# Power_and_Clocks.net
KiCad netlist of a schematic drawn in Altium Designer
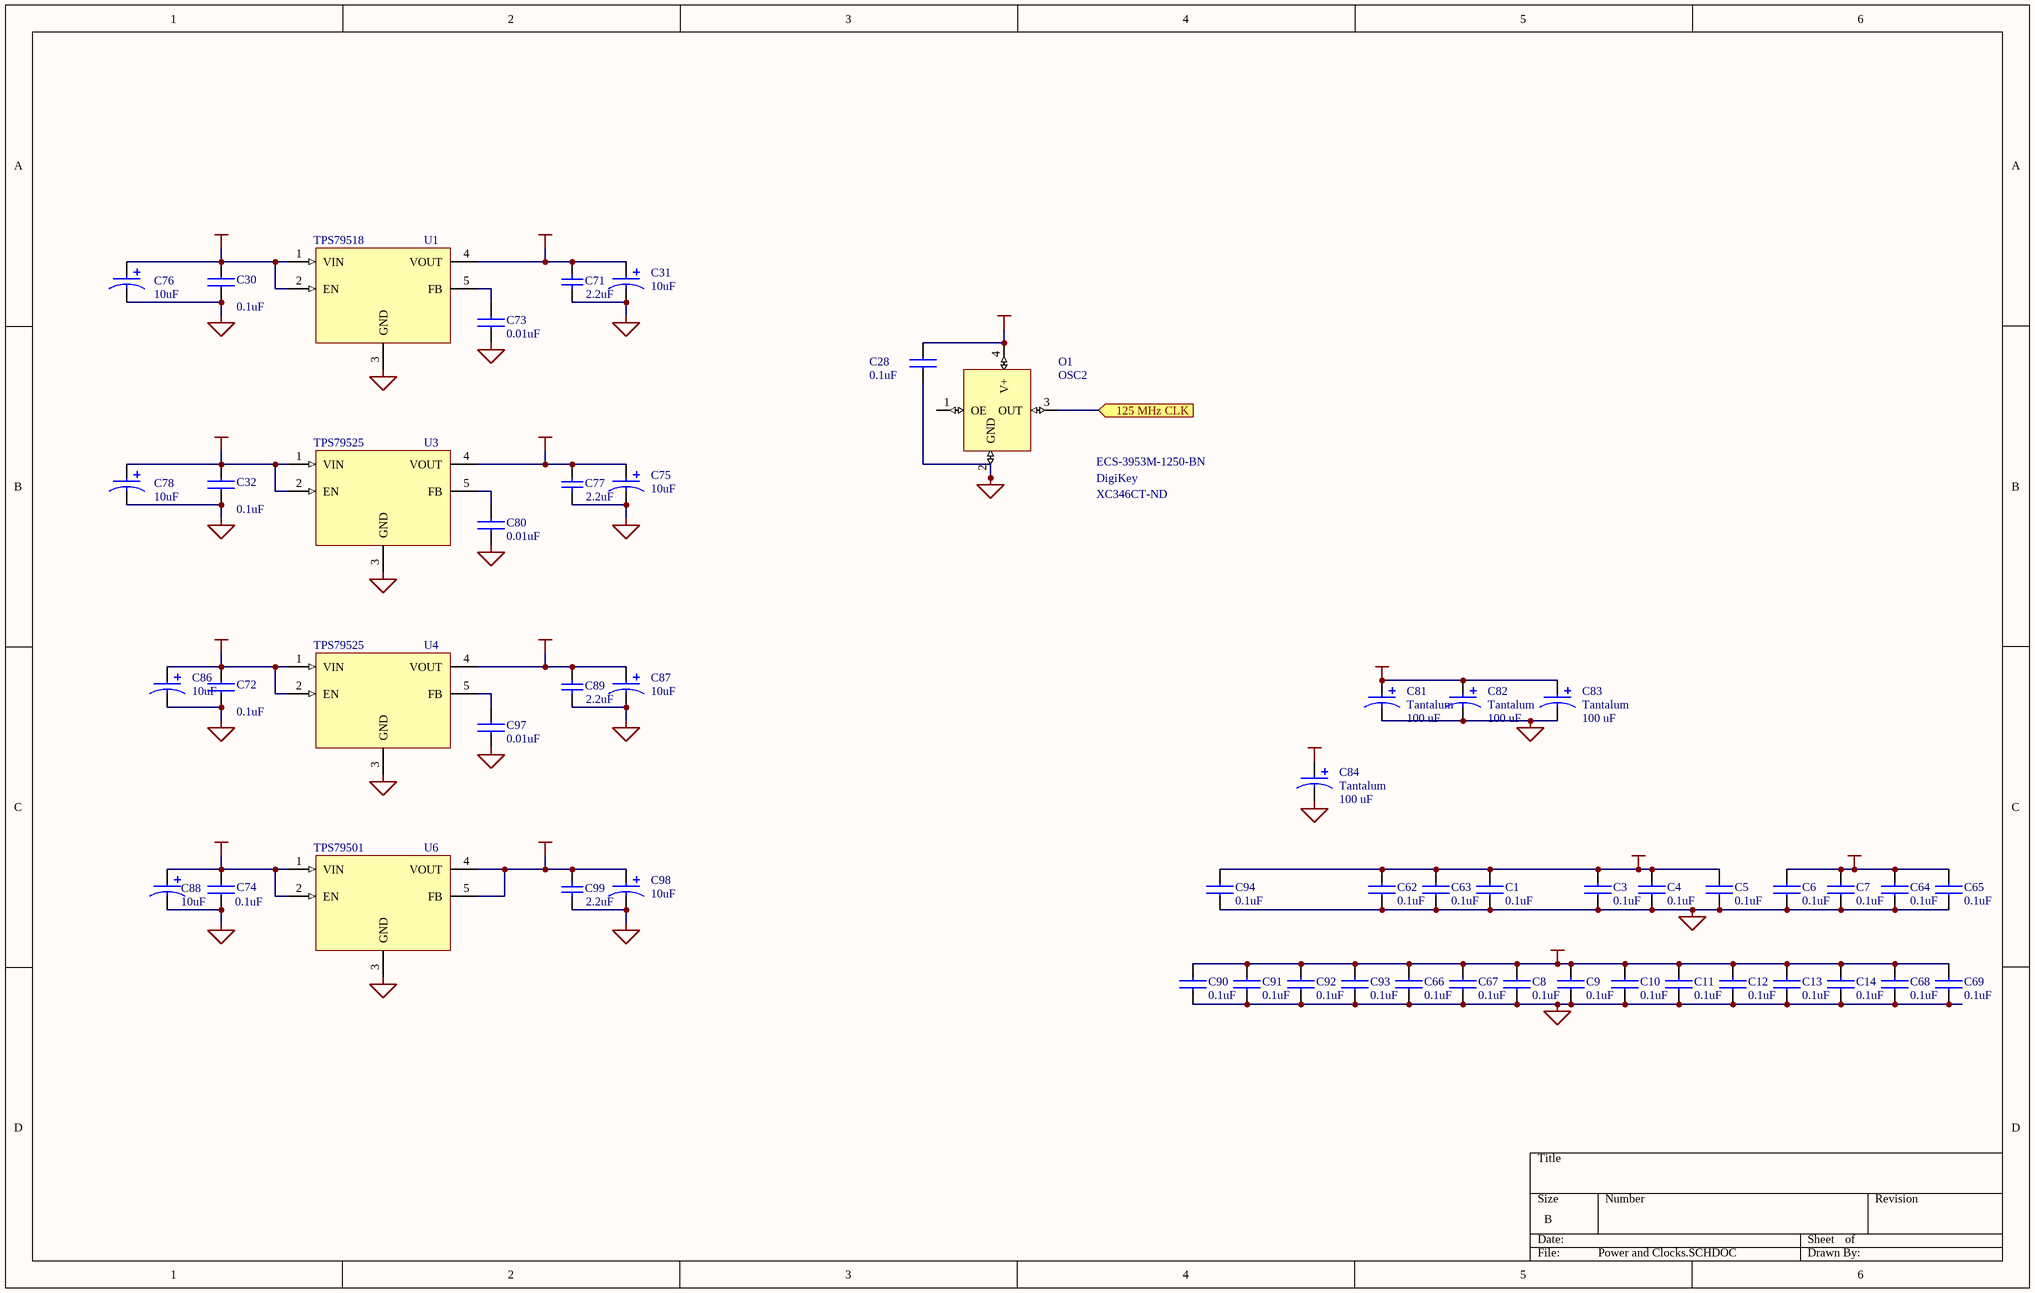
[diagram p0: Power and Clocks.SCHDOC]

(export (version "E")
  (design (tool "Eeschema 10.0.6"))
  (components
    (comp (ref "C1")
      (value "0.1uF")
      (footprint "0603")
      (description "Standard Capacitor")
      (fields (field (name "Comment") "CAPACITOR"))
      (libsource (lib "parts") (part "CAPACITOR"))
    )
    (comp (ref "C3")
      (value "0.1uF")
      (footprint "0603")
      (description "Standard Capacitor")
      (fields (field (name "Comment") "CAPACITOR"))
      (libsource (lib "parts") (part "CAPACITOR"))
    )
    (comp (ref "C4")
      (value "0.1uF")
      (footprint "0603")
      (description "Standard Capacitor")
      (fields (field (name "Comment") "CAPACITOR"))
      (libsource (lib "parts") (part "CAPACITOR"))
    )
    (comp (ref "C5")
      (value "0.1uF")
      (footprint "0603")
      (description "Standard Capacitor")
      (fields (field (name "Comment") "CAPACITOR"))
      (libsource (lib "parts") (part "CAPACITOR"))
    )
    (comp (ref "C6")
      (value "0.1uF")
      (footprint "0603")
      (description "Standard Capacitor")
      (fields (field (name "Comment") "CAPACITOR"))
      (libsource (lib "parts") (part "CAPACITOR"))
    )
    (comp (ref "C7")
      (value "0.1uF")
      (footprint "0603")
      (description "Standard Capacitor")
      (fields (field (name "Comment") "CAPACITOR"))
      (libsource (lib "parts") (part "CAPACITOR"))
    )
    (comp (ref "C8")
      (value "0.1uF")
      (footprint "0603")
      (description "Standard Capacitor")
      (fields (field (name "Comment") "CAPACITOR"))
      (libsource (lib "parts") (part "CAPACITOR"))
    )
    (comp (ref "C9")
      (value "0.1uF")
      (footprint "0603")
      (description "Standard Capacitor")
      (fields (field (name "Comment") "CAPACITOR"))
      (libsource (lib "parts") (part "CAPACITOR"))
    )
    (comp (ref "C10")
      (value "0.1uF")
      (footprint "0603")
      (description "Standard Capacitor")
      (fields (field (name "Comment") "CAPACITOR"))
      (libsource (lib "parts") (part "CAPACITOR"))
    )
    (comp (ref "C11")
      (value "0.1uF")
      (footprint "0603")
      (description "Standard Capacitor")
      (fields (field (name "Comment") "CAPACITOR"))
      (libsource (lib "parts") (part "CAPACITOR"))
    )
    (comp (ref "C12")
      (value "0.1uF")
      (footprint "0603")
      (description "Standard Capacitor")
      (fields (field (name "Comment") "CAPACITOR"))
      (libsource (lib "parts") (part "CAPACITOR"))
    )
    (comp (ref "C13")
      (value "0.1uF")
      (footprint "0603")
      (description "Standard Capacitor")
      (fields (field (name "Comment") "CAPACITOR"))
      (libsource (lib "parts") (part "CAPACITOR"))
    )
    (comp (ref "C14")
      (value "0.1uF")
      (footprint "0603")
      (description "Standard Capacitor")
      (fields (field (name "Comment") "CAPACITOR"))
      (libsource (lib "parts") (part "CAPACITOR"))
    )
    (comp (ref "C28")
      (value "0.1uF")
      (footprint "0603")
      (description "Standard Capacitor")
      (fields (field (name "Comment") "CAPACITOR"))
      (libsource (lib "parts") (part "CAPACITOR"))
    )
    (comp (ref "C30")
      (value "0.1uF")
      (footprint "0603")
      (description "Standard Capacitor")
      (fields (field (name "Comment") "CAPACITOR"))
      (libsource (lib "parts") (part "CAPACITOR"))
    )
    (comp (ref "C31")
      (value "10uF")
      (footprint "6032")
      (description "Standard Capacitor")
      (fields (field (name "Comment") "POLCAP2"))
      (libsource (lib "parts") (part "POLCAP2"))
    )
    (comp (ref "C32")
      (value "0.1uF")
      (footprint "0603")
      (description "Standard Capacitor")
      (fields (field (name "Comment") "CAPACITOR"))
      (libsource (lib "parts") (part "CAPACITOR"))
    )
    (comp (ref "C62")
      (value "0.1uF")
      (footprint "0603")
      (description "Standard Capacitor")
      (fields (field (name "Comment") "CAPACITOR"))
      (libsource (lib "parts") (part "CAPACITOR"))
    )
    (comp (ref "C63")
      (value "0.1uF")
      (footprint "0603")
      (description "Standard Capacitor")
      (fields (field (name "Comment") "CAPACITOR"))
      (libsource (lib "parts") (part "CAPACITOR"))
    )
    (comp (ref "C64")
      (value "0.1uF")
      (footprint "0603")
      (description "Standard Capacitor")
      (fields (field (name "Comment") "CAPACITOR"))
      (libsource (lib "parts") (part "CAPACITOR"))
    )
    (comp (ref "C65")
      (value "0.1uF")
      (footprint "0603")
      (description "Standard Capacitor")
      (fields (field (name "Comment") "CAPACITOR"))
      (libsource (lib "parts") (part "CAPACITOR"))
    )
    (comp (ref "C66")
      (value "0.1uF")
      (footprint "0603")
      (description "Standard Capacitor")
      (fields (field (name "Comment") "CAPACITOR"))
      (libsource (lib "parts") (part "CAPACITOR"))
    )
    (comp (ref "C67")
      (value "0.1uF")
      (footprint "0603")
      (description "Standard Capacitor")
      (fields (field (name "Comment") "CAPACITOR"))
      (libsource (lib "parts") (part "CAPACITOR"))
    )
    (comp (ref "C68")
      (value "0.1uF")
      (footprint "0603")
      (description "Standard Capacitor")
      (fields (field (name "Comment") "CAPACITOR"))
      (libsource (lib "parts") (part "CAPACITOR"))
    )
    (comp (ref "C69")
      (value "0.1uF")
      (footprint "0603")
      (description "Standard Capacitor")
      (fields (field (name "Comment") "CAPACITOR"))
      (libsource (lib "parts") (part "CAPACITOR"))
    )
    (comp (ref "C71")
      (value "2.2uF")
      (footprint "1206")
      (description "Capacitor")
      (fields
        (field (name "MANUFACTURER") "Generic Components")
        (field (name "Comment") "Cap")
        (field (name "PUBLISHER") "Altium Limited")
      )
      (libsource (lib "Miscellaneous Devices") (part "Cap"))
    )
    (comp (ref "C72")
      (value "0.1uF")
      (footprint "0603")
      (description "Standard Capacitor")
      (fields (field (name "Comment") "CAPACITOR"))
      (libsource (lib "parts") (part "CAPACITOR"))
    )
    (comp (ref "C73")
      (value "0.01uF")
      (footprint "0402")
      (description "Standard Capacitor")
      (fields (field (name "Comment") "CAPACITOR"))
      (libsource (lib "parts") (part "CAPACITOR"))
    )
    (comp (ref "C74")
      (value "0.1uF")
      (footprint "0603")
      (description "Standard Capacitor")
      (fields (field (name "Comment") "CAPACITOR"))
      (libsource (lib "parts") (part "CAPACITOR"))
    )
    (comp (ref "C75")
      (value "10uF")
      (footprint "6032")
      (description "Standard Capacitor")
      (fields (field (name "Comment") "POLCAP2"))
      (libsource (lib "parts") (part "POLCAP2"))
    )
    (comp (ref "C76")
      (value "10uF")
      (footprint "6032")
      (description "Standard Capacitor")
      (fields (field (name "Comment") "POLCAP2"))
      (libsource (lib "parts") (part "POLCAP2"))
    )
    (comp (ref "C77")
      (value "2.2uF")
      (footprint "1206")
      (description "Capacitor")
      (fields
        (field (name "MANUFACTURER") "Generic Components")
        (field (name "Comment") "Cap")
        (field (name "PUBLISHER") "Altium Limited")
      )
      (libsource (lib "Miscellaneous Devices") (part "Cap"))
    )
    (comp (ref "C78")
      (value "10uF")
      (footprint "6032")
      (description "Standard Capacitor")
      (fields (field (name "Comment") "POLCAP2"))
      (libsource (lib "parts") (part "POLCAP2"))
    )
    (comp (ref "C80")
      (value "0.01uF")
      (footprint "0402")
      (description "Standard Capacitor")
      (fields (field (name "Comment") "CAPACITOR"))
      (libsource (lib "parts") (part "CAPACITOR"))
    )
    (comp (ref "C81")
      (value "Tantalum")
      (footprint "6032")
      (description "Standard Capacitor")
      (fields (field (name "ALTIUM_VALUE") "100 uF"))
      (libsource (lib "parts") (part "POLCAP2"))
    )
    (comp (ref "C82")
      (value "Tantalum")
      (footprint "6032")
      (description "Standard Capacitor")
      (fields (field (name "ALTIUM_VALUE") "100 uF"))
      (libsource (lib "parts") (part "POLCAP2"))
    )
    (comp (ref "C83")
      (value "Tantalum")
      (footprint "6032")
      (description "Standard Capacitor")
      (fields (field (name "ALTIUM_VALUE") "100 uF"))
      (libsource (lib "parts") (part "POLCAP2"))
    )
    (comp (ref "C84")
      (value "Tantalum")
      (footprint "6032")
      (description "Standard Capacitor")
      (fields (field (name "ALTIUM_VALUE") "100 uF"))
      (libsource (lib "parts") (part "POLCAP2"))
    )
    (comp (ref "C86")
      (value "10uF")
      (footprint "6032")
      (description "Standard Capacitor")
      (fields (field (name "Comment") "POLCAP2"))
      (libsource (lib "parts") (part "POLCAP2"))
    )
    (comp (ref "C87")
      (value "10uF")
      (footprint "6032")
      (description "Standard Capacitor")
      (fields (field (name "Comment") "POLCAP2"))
      (libsource (lib "parts") (part "POLCAP2"))
    )
    (comp (ref "C88")
      (value "10uF")
      (footprint "6032")
      (description "Standard Capacitor")
      (fields (field (name "Comment") "POLCAP2"))
      (libsource (lib "parts") (part "POLCAP2"))
    )
    (comp (ref "C89")
      (value "2.2uF")
      (footprint "1206")
      (description "Capacitor")
      (fields
        (field (name "MANUFACTURER") "Generic Components")
        (field (name "Comment") "Cap")
        (field (name "PUBLISHER") "Altium Limited")
      )
      (libsource (lib "Miscellaneous Devices") (part "Cap"))
    )
    (comp (ref "C90")
      (value "0.1uF")
      (footprint "0603")
      (description "Standard Capacitor")
      (fields (field (name "Comment") "CAPACITOR"))
      (libsource (lib "parts") (part "CAPACITOR"))
    )
    (comp (ref "C91")
      (value "0.1uF")
      (footprint "0603")
      (description "Standard Capacitor")
      (fields (field (name "Comment") "CAPACITOR"))
      (libsource (lib "parts") (part "CAPACITOR"))
    )
    (comp (ref "C92")
      (value "0.1uF")
      (footprint "0603")
      (description "Standard Capacitor")
      (fields (field (name "Comment") "CAPACITOR"))
      (libsource (lib "parts") (part "CAPACITOR"))
    )
    (comp (ref "C93")
      (value "0.1uF")
      (footprint "0603")
      (description "Standard Capacitor")
      (fields (field (name "Comment") "CAPACITOR"))
      (libsource (lib "parts") (part "CAPACITOR"))
    )
    (comp (ref "C94")
      (value "0.1uF")
      (footprint "0603")
      (description "Standard Capacitor")
      (fields (field (name "Comment") "CAPACITOR"))
      (libsource (lib "parts") (part "CAPACITOR"))
    )
    (comp (ref "C97")
      (value "0.01uF")
      (footprint "0402")
      (description "Standard Capacitor")
      (fields (field (name "Comment") "CAPACITOR"))
      (libsource (lib "parts") (part "CAPACITOR"))
    )
    (comp (ref "C98")
      (value "10uF")
      (footprint "6032")
      (description "Standard Capacitor")
      (fields (field (name "Comment") "POLCAP2"))
      (libsource (lib "parts") (part "POLCAP2"))
    )
    (comp (ref "C99")
      (value "2.2uF")
      (footprint "1206")
      (description "Capacitor")
      (fields
        (field (name "MANUFACTURER") "Generic Components")
        (field (name "Comment") "Cap")
        (field (name "PUBLISHER") "Altium Limited")
      )
      (libsource (lib "Miscellaneous Devices") (part "Cap"))
    )
    (comp (ref "O1")
      (value "OSC2")
      (footprint "ECS-3953M")
      (description "ECS SMD Oscillator, ECS-3953M")
      (fields
        (field (name "PART") "ECS-3953M-1250-BN")
        (field (name "VENDOR") "DigiKey")
        (field (name "VENDORPART") "XC346CT-ND")
      )
      (libsource (lib "My devices") (part "OSC2"))
    )
    (comp (ref "U1")
      (value "TPS79518")
      (footprint "SOT223-5/Simple")
      (description "TI Ultra-low-noise LDO")
      (libsource (lib "parts") (part "TPS795XX"))
    )
    (comp (ref "U3")
      (value "TPS79525")
      (footprint "SOT223-5/Simple")
      (description "TI Ultra-low-noise LDO")
      (libsource (lib "parts") (part "TPS795XX"))
    )
    (comp (ref "U4")
      (value "TPS79525")
      (footprint "SOT223-5/Simple")
      (description "TI Ultra-low-noise LDO")
      (libsource (lib "parts") (part "TPS795XX"))
    )
    (comp (ref "U6")
      (value "TPS79501")
      (footprint "SOT223-5/Simple")
      (description "TI Ultra-low-noise LDO")
      (libsource (lib "parts") (part "TPS795XX"))
    )
  )
  (nets
    (net (code "1") (name "+1.2VCC") (class "Default")
      (node (ref "C6") (pin "2") (pintype "passive"))
      (node (ref "C64") (pin "2") (pintype "passive"))
      (node (ref "C65") (pin "2") (pintype "passive"))
      (node (ref "C7") (pin "2") (pintype "passive"))
      (node (ref "C98") (pin "1") (pintype "passive"))
      (node (ref "C99") (pin "2") (pinfunction "2_2") (pintype "passive"))
      (node (ref "U6") (pin "4") (pinfunction "VOUT_4") (pintype "power_in"))
      (node (ref "U6") (pin "5") (pinfunction "FB_5") (pintype "passive"))
    )
    (net (code "2") (name "+1.8VCC") (class "Default")
      (node (ref "C31") (pin "1") (pintype "passive"))
      (node (ref "C71") (pin "2") (pinfunction "2_2") (pintype "passive"))
      (node (ref "C84") (pin "1") (pintype "passive"))
      (node (ref "U1") (pin "4") (pinfunction "VOUT_4") (pintype "power_in"))
    )
    (net (code "3") (name "+2.5VCC") (class "Default")
      (node (ref "C1") (pin "2") (pintype "passive"))
      (node (ref "C3") (pin "2") (pintype "passive"))
      (node (ref "C4") (pin "2") (pintype "passive"))
      (node (ref "C5") (pin "2") (pintype "passive"))
      (node (ref "C62") (pin "2") (pintype "passive"))
      (node (ref "C63") (pin "2") (pintype "passive"))
      (node (ref "C75") (pin "1") (pintype "passive"))
      (node (ref "C77") (pin "2") (pinfunction "2_2") (pintype "passive"))
      (node (ref "C94") (pin "2") (pintype "passive"))
      (node (ref "U3") (pin "4") (pinfunction "VOUT_4") (pintype "power_in"))
    )
    (net (code "4") (name "+2.5VPHY") (class "Default")
      (node (ref "C87") (pin "1") (pintype "passive"))
      (node (ref "C89") (pin "2") (pinfunction "2_2") (pintype "passive"))
      (node (ref "U4") (pin "4") (pinfunction "VOUT_4") (pintype "power_in"))
    )
    (net (code "5") (name "/125 MHz CLK") (class "Default")
      (node (ref "O1") (pin "3") (pinfunction "OUT_3") (pintype "bidirectional"))
    )
    (net (code "6") (name "GND") (class "Default")
      (node (ref "C1") (pin "1") (pintype "passive"))
      (node (ref "C10") (pin "1") (pintype "passive"))
      (node (ref "C11") (pin "1") (pintype "passive"))
      (node (ref "C12") (pin "1") (pintype "passive"))
      (node (ref "C13") (pin "1") (pintype "passive"))
      (node (ref "C14") (pin "1") (pintype "passive"))
      (node (ref "C28") (pin "1") (pintype "passive"))
      (node (ref "C3") (pin "1") (pintype "passive"))
      (node (ref "C30") (pin "1") (pintype "passive"))
      (node (ref "C31") (pin "2") (pintype "passive"))
      (node (ref "C32") (pin "1") (pintype "passive"))
      (node (ref "C4") (pin "1") (pintype "passive"))
      (node (ref "C5") (pin "1") (pintype "passive"))
      (node (ref "C6") (pin "1") (pintype "passive"))
      (node (ref "C62") (pin "1") (pintype "passive"))
      (node (ref "C63") (pin "1") (pintype "passive"))
      (node (ref "C64") (pin "1") (pintype "passive"))
      (node (ref "C65") (pin "1") (pintype "passive"))
      (node (ref "C66") (pin "1") (pintype "passive"))
      (node (ref "C67") (pin "1") (pintype "passive"))
      (node (ref "C68") (pin "1") (pintype "passive"))
      (node (ref "C69") (pin "1") (pintype "passive"))
      (node (ref "C7") (pin "1") (pintype "passive"))
      (node (ref "C71") (pin "1") (pinfunction "1_1") (pintype "passive"))
      (node (ref "C72") (pin "1") (pintype "passive"))
      (node (ref "C73") (pin "1") (pintype "passive"))
      (node (ref "C74") (pin "1") (pintype "passive"))
      (node (ref "C75") (pin "2") (pintype "passive"))
      (node (ref "C76") (pin "2") (pintype "passive"))
      (node (ref "C77") (pin "1") (pinfunction "1_1") (pintype "passive"))
      (node (ref "C78") (pin "2") (pintype "passive"))
      (node (ref "C8") (pin "1") (pintype "passive"))
      (node (ref "C80") (pin "1") (pintype "passive"))
      (node (ref "C81") (pin "2") (pintype "passive"))
      (node (ref "C82") (pin "2") (pintype "passive"))
      (node (ref "C83") (pin "2") (pintype "passive"))
      (node (ref "C84") (pin "2") (pintype "passive"))
      (node (ref "C86") (pin "2") (pintype "passive"))
      (node (ref "C87") (pin "2") (pintype "passive"))
      (node (ref "C88") (pin "2") (pintype "passive"))
      (node (ref "C89") (pin "1") (pinfunction "1_1") (pintype "passive"))
      (node (ref "C9") (pin "1") (pintype "passive"))
      (node (ref "C90") (pin "1") (pintype "passive"))
      (node (ref "C91") (pin "1") (pintype "passive"))
      (node (ref "C92") (pin "1") (pintype "passive"))
      (node (ref "C93") (pin "1") (pintype "passive"))
      (node (ref "C94") (pin "1") (pintype "passive"))
      (node (ref "C97") (pin "1") (pintype "passive"))
      (node (ref "C98") (pin "2") (pintype "passive"))
      (node (ref "C99") (pin "1") (pinfunction "1_1") (pintype "passive"))
      (node (ref "O1") (pin "2") (pinfunction "GND_2") (pintype "bidirectional"))
      (node (ref "U1") (pin "3") (pinfunction "GND_3") (pintype "power_in"))
      (node (ref "U3") (pin "3") (pinfunction "GND_3") (pintype "power_in"))
      (node (ref "U4") (pin "3") (pinfunction "GND_3") (pintype "power_in"))
      (node (ref "U6") (pin "3") (pinfunction "GND_3") (pintype "power_in"))
    )
    (net (code "7") (name "Net-(U1-FB)") (class "Default")
      (node (ref "C73") (pin "2") (pintype "passive"))
      (node (ref "U1") (pin "5") (pinfunction "FB_5") (pintype "passive"))
    )
    (net (code "8") (name "Net-(U3-FB)") (class "Default")
      (node (ref "C80") (pin "2") (pintype "passive"))
      (node (ref "U3") (pin "5") (pinfunction "FB_5") (pintype "passive"))
    )
    (net (code "9") (name "Net-(U4-FB)") (class "Default")
      (node (ref "C97") (pin "2") (pintype "passive"))
      (node (ref "U4") (pin "5") (pinfunction "FB_5") (pintype "passive"))
    )
    (net (code "10") (name "VCC") (class "Default")
      (node (ref "C10") (pin "2") (pintype "passive"))
      (node (ref "C11") (pin "2") (pintype "passive"))
      (node (ref "C12") (pin "2") (pintype "passive"))
      (node (ref "C13") (pin "2") (pintype "passive"))
      (node (ref "C14") (pin "2") (pintype "passive"))
      (node (ref "C28") (pin "2") (pintype "passive"))
      (node (ref "C30") (pin "2") (pintype "passive"))
      (node (ref "C32") (pin "2") (pintype "passive"))
      (node (ref "C66") (pin "2") (pintype "passive"))
      (node (ref "C67") (pin "2") (pintype "passive"))
      (node (ref "C68") (pin "2") (pintype "passive"))
      (node (ref "C69") (pin "2") (pintype "passive"))
      (node (ref "C72") (pin "2") (pintype "passive"))
      (node (ref "C74") (pin "2") (pintype "passive"))
      (node (ref "C76") (pin "1") (pintype "passive"))
      (node (ref "C78") (pin "1") (pintype "passive"))
      (node (ref "C8") (pin "2") (pintype "passive"))
      (node (ref "C81") (pin "1") (pintype "passive"))
      (node (ref "C82") (pin "1") (pintype "passive"))
      (node (ref "C83") (pin "1") (pintype "passive"))
      (node (ref "C86") (pin "1") (pintype "passive"))
      (node (ref "C88") (pin "1") (pintype "passive"))
      (node (ref "C9") (pin "2") (pintype "passive"))
      (node (ref "C90") (pin "2") (pintype "passive"))
      (node (ref "C91") (pin "2") (pintype "passive"))
      (node (ref "C92") (pin "2") (pintype "passive"))
      (node (ref "C93") (pin "2") (pintype "passive"))
      (node (ref "O1") (pin "4") (pinfunction "V+_4") (pintype "bidirectional"))
      (node (ref "U1") (pin "1") (pinfunction "VIN_1") (pintype "input"))
      (node (ref "U1") (pin "2") (pinfunction "EN_2") (pintype "input"))
      (node (ref "U3") (pin "1") (pinfunction "VIN_1") (pintype "input"))
      (node (ref "U3") (pin "2") (pinfunction "EN_2") (pintype "input"))
      (node (ref "U4") (pin "1") (pinfunction "VIN_1") (pintype "input"))
      (node (ref "U4") (pin "2") (pinfunction "EN_2") (pintype "input"))
      (node (ref "U6") (pin "1") (pinfunction "VIN_1") (pintype "input"))
      (node (ref "U6") (pin "2") (pinfunction "EN_2") (pintype "input"))
    )
    (net (code "11") (name "unconnected-(O1-OE-Pad1)") (class "Default")
      (node (ref "O1") (pin "1") (pinfunction "OE_1") (pintype "bidirectional"))
    )
  )
)
